# Analog_to_Digital_Con.net
KiCad netlist of a schematic drawn in Altium Designer
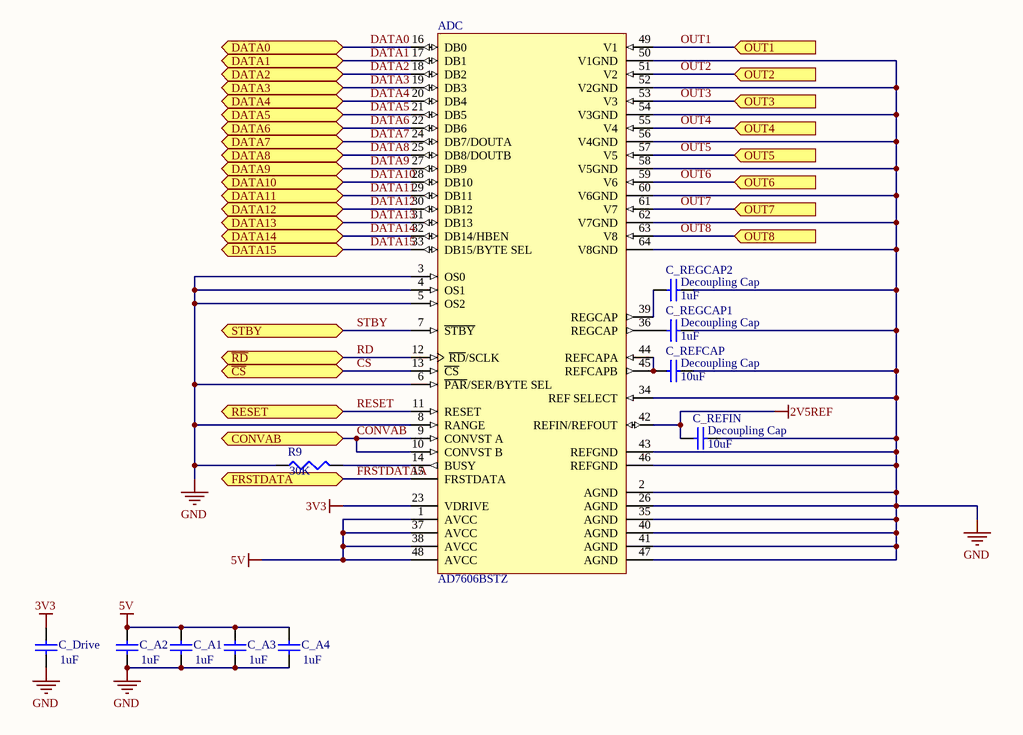
[diagram p0: Analog to Digital Con.SchDoc]

(export (version "E")
  (design (tool "Eeschema 10.0.6"))
  (components
    (comp (ref "ADC")
      (value "AD7606BSTZ")
      (footprint "ST-64-2_N")
      (fields (field (name "GENERIC PART NUMBER") "AD7606") (field (name "MANUFACTURER") "Analog Devices"))
      (libsource (lib "Analog Devices Data Converters Analog-to-Digital Converters") (part "AD7606BSTZ"))
    )
    (comp (ref "C_A1")
      (value "1uF")
      (footprint "6-0805_N")
      (description "Capacitor (Semiconductor SIM Model)")
      (fields (field (name "Comment") "Decoupling Cap") (field (name "PUBLISHER") "Altium Limited"))
      (libsource (lib "Miscellaneous Devices") (part "Cap Semi"))
    )
    (comp (ref "C_A2")
      (value "1uF")
      (footprint "6-0805_N")
      (description "Capacitor (Semiconductor SIM Model)")
      (fields (field (name "Comment") "Decoupling Cap") (field (name "PUBLISHER") "Altium Limited"))
      (libsource (lib "Miscellaneous Devices") (part "Cap Semi"))
    )
    (comp (ref "C_A3")
      (value "1uF")
      (footprint "6-0805_N")
      (description "Capacitor (Semiconductor SIM Model)")
      (fields (field (name "Comment") "Decoupling Cap") (field (name "PUBLISHER") "Altium Limited"))
      (libsource (lib "Miscellaneous Devices") (part "Cap Semi"))
    )
    (comp (ref "C_A4")
      (value "1uF")
      (footprint "6-0805_N")
      (description "Capacitor (Semiconductor SIM Model)")
      (fields (field (name "Comment") "Decoupling Cap") (field (name "PUBLISHER") "Altium Limited"))
      (libsource (lib "Miscellaneous Devices") (part "Cap Semi"))
    )
    (comp (ref "C_Drive")
      (value "1uF")
      (footprint "6-0805_N")
      (description "Capacitor (Semiconductor SIM Model)")
      (fields (field (name "Comment") "Decoupling Cap") (field (name "PUBLISHER") "Altium Limited"))
      (libsource (lib "Miscellaneous Devices") (part "Cap Semi"))
    )
    (comp (ref "C_REFCAP")
      (value "Decoupling Cap")
      (footprint "6-0805_N")
      (description "Capacitor (Semiconductor SIM Model)")
      (fields (field (name "ALTIUM_VALUE") "10uF") (field (name "PUBLISHER") "Altium Limited"))
      (libsource (lib "Miscellaneous Devices") (part "Cap Semi"))
    )
    (comp (ref "C_REFIN")
      (value "Decoupling Cap")
      (footprint "6-0805_N")
      (description "Capacitor (Semiconductor SIM Model)")
      (fields (field (name "ALTIUM_VALUE") "10uF") (field (name "PUBLISHER") "Altium Limited"))
      (libsource (lib "Miscellaneous Devices") (part "Cap Semi"))
    )
    (comp (ref "C_REGCAP1")
      (value "Decoupling Cap")
      (footprint "6-0805_N")
      (description "Capacitor (Semiconductor SIM Model)")
      (fields (field (name "ALTIUM_VALUE") "1uF") (field (name "PUBLISHER") "Altium Limited"))
      (libsource (lib "Miscellaneous Devices") (part "Cap Semi"))
    )
    (comp (ref "C_REGCAP2")
      (value "Decoupling Cap")
      (footprint "6-0805_N")
      (description "Capacitor (Semiconductor SIM Model)")
      (fields (field (name "ALTIUM_VALUE") "1uF") (field (name "PUBLISHER") "Altium Limited"))
      (libsource (lib "Miscellaneous Devices") (part "Cap Semi"))
    )
    (comp (ref "R9")
      (value "30K")
      (footprint "6-0805_N")
      (description "Resistor")
      (fields (field (name "Comment") "Res3") (field (name "PUBLISHER") "Altium Limited"))
      (libsource (lib "Miscellaneous Devices") (part "Res3"))
    )
  )
  (nets
    (net (code "1") (name "/CONVAB") (class "Default")
      (node (ref "ADC") (pin "10") (pinfunction "CONVST_B_10") (pintype "input"))
      (node (ref "ADC") (pin "9") (pinfunction "CONVST_A_9") (pintype "input"))
    )
    (net (code "2") (name "/CS") (class "Default")
      (node (ref "ADC") (pin "13") (pinfunction "~{CS}_13") (pintype "input"))
    )
    (net (code "3") (name "/DATA0") (class "Default")
      (node (ref "ADC") (pin "16") (pinfunction "DB0_16") (pintype "bidirectional"))
    )
    (net (code "4") (name "/DATA1") (class "Default")
      (node (ref "ADC") (pin "17") (pinfunction "DB1_17") (pintype "bidirectional"))
    )
    (net (code "5") (name "/DATA2") (class "Default")
      (node (ref "ADC") (pin "18") (pinfunction "DB2_18") (pintype "bidirectional"))
    )
    (net (code "6") (name "/DATA3") (class "Default")
      (node (ref "ADC") (pin "19") (pinfunction "DB3_19") (pintype "bidirectional"))
    )
    (net (code "7") (name "/DATA4") (class "Default")
      (node (ref "ADC") (pin "20") (pinfunction "DB4_20") (pintype "bidirectional"))
    )
    (net (code "8") (name "/DATA5") (class "Default")
      (node (ref "ADC") (pin "21") (pinfunction "DB5_21") (pintype "bidirectional"))
    )
    (net (code "9") (name "/DATA6") (class "Default")
      (node (ref "ADC") (pin "22") (pinfunction "DB6_22") (pintype "bidirectional"))
    )
    (net (code "10") (name "/DATA7") (class "Default")
      (node (ref "ADC") (pin "24") (pinfunction "DB7/DOUTA_24") (pintype "bidirectional"))
    )
    (net (code "11") (name "/DATA8") (class "Default")
      (node (ref "ADC") (pin "25") (pinfunction "DB8/DOUTB_25") (pintype "bidirectional"))
    )
    (net (code "12") (name "/DATA9") (class "Default")
      (node (ref "ADC") (pin "27") (pinfunction "DB9_27") (pintype "bidirectional"))
    )
    (net (code "13") (name "/DATA10") (class "Default")
      (node (ref "ADC") (pin "28") (pinfunction "DB10_28") (pintype "bidirectional"))
    )
    (net (code "14") (name "/DATA11") (class "Default")
      (node (ref "ADC") (pin "29") (pinfunction "DB11_29") (pintype "bidirectional"))
    )
    (net (code "15") (name "/DATA12") (class "Default")
      (node (ref "ADC") (pin "30") (pinfunction "DB12_30") (pintype "bidirectional"))
    )
    (net (code "16") (name "/DATA13") (class "Default")
      (node (ref "ADC") (pin "31") (pinfunction "DB13_31") (pintype "bidirectional"))
    )
    (net (code "17") (name "/DATA14") (class "Default")
      (node (ref "ADC") (pin "32") (pinfunction "DB14/HBEN_32") (pintype "bidirectional"))
    )
    (net (code "18") (name "/DATA15") (class "Default")
      (node (ref "ADC") (pin "33") (pinfunction "DB15/BYTE_SEL_33") (pintype "bidirectional"))
    )
    (net (code "19") (name "/FRSTDATAA") (class "Default")
      (node (ref "ADC") (pin "15") (pinfunction "FRSTDATA_15") (pintype "tri_state"))
    )
    (net (code "20") (name "/OUT1") (class "Default")
      (node (ref "ADC") (pin "49") (pinfunction "V1_49") (pintype "input"))
    )
    (net (code "21") (name "/OUT2") (class "Default")
      (node (ref "ADC") (pin "51") (pinfunction "V2_51") (pintype "input"))
    )
    (net (code "22") (name "/OUT3") (class "Default")
      (node (ref "ADC") (pin "53") (pinfunction "V3_53") (pintype "input"))
    )
    (net (code "23") (name "/OUT4") (class "Default")
      (node (ref "ADC") (pin "55") (pinfunction "V4_55") (pintype "input"))
    )
    (net (code "24") (name "/OUT5") (class "Default")
      (node (ref "ADC") (pin "57") (pinfunction "V5_57") (pintype "input"))
    )
    (net (code "25") (name "/OUT6") (class "Default")
      (node (ref "ADC") (pin "59") (pinfunction "V6_59") (pintype "input"))
    )
    (net (code "26") (name "/OUT7") (class "Default")
      (node (ref "ADC") (pin "61") (pinfunction "V7_61") (pintype "input"))
    )
    (net (code "27") (name "/OUT8") (class "Default")
      (node (ref "ADC") (pin "63") (pinfunction "V8_63") (pintype "input"))
    )
    (net (code "28") (name "/RD") (class "Default")
      (node (ref "ADC") (pin "12") (pinfunction "~{RD}/SCLK_12") (pintype "input"))
    )
    (net (code "29") (name "/RESET") (class "Default")
      (node (ref "ADC") (pin "11") (pinfunction "RESET_11") (pintype "input"))
    )
    (net (code "30") (name "/STBY") (class "Default")
      (node (ref "ADC") (pin "7") (pinfunction "~{STBY}_7") (pintype "input"))
    )
    (net (code "31") (name "2V5REF") (class "Default")
      (node (ref "ADC") (pin "42") (pinfunction "REFIN/REFOUT_42") (pintype "bidirectional"))
      (node (ref "C_REFIN") (pin "2") (pinfunction "2_2") (pintype "passive"))
    )
    (net (code "32") (name "3V3") (class "Default")
      (node (ref "ADC") (pin "23") (pinfunction "VDRIVE_23") (pintype "power_in"))
      (node (ref "C_Drive") (pin "1") (pinfunction "1_1") (pintype "passive"))
    )
    (net (code "33") (name "5V") (class "Default")
      (node (ref "ADC") (pin "1") (pinfunction "AVCC_1") (pintype "power_in"))
      (node (ref "ADC") (pin "37") (pinfunction "AVCC_37") (pintype "power_in"))
      (node (ref "ADC") (pin "38") (pinfunction "AVCC_38") (pintype "power_in"))
      (node (ref "ADC") (pin "48") (pinfunction "AVCC_48") (pintype "power_in"))
      (node (ref "C_A1") (pin "1") (pinfunction "1_1") (pintype "passive"))
      (node (ref "C_A2") (pin "1") (pinfunction "1_1") (pintype "passive"))
      (node (ref "C_A3") (pin "1") (pinfunction "1_1") (pintype "passive"))
      (node (ref "C_A4") (pin "1") (pinfunction "1_1") (pintype "passive"))
    )
    (net (code "34") (name "GND") (class "Default")
      (node (ref "ADC") (pin "2") (pinfunction "AGND_2") (pintype "power_in"))
      (node (ref "ADC") (pin "26") (pinfunction "AGND_26") (pintype "power_in"))
      (node (ref "ADC") (pin "3") (pinfunction "OS0_3") (pintype "input"))
      (node (ref "ADC") (pin "34") (pinfunction "REF_SELECT_34") (pintype "input"))
      (node (ref "ADC") (pin "35") (pinfunction "AGND_35") (pintype "power_in"))
      (node (ref "ADC") (pin "4") (pinfunction "OS1_4") (pintype "input"))
      (node (ref "ADC") (pin "40") (pinfunction "AGND_40") (pintype "power_in"))
      (node (ref "ADC") (pin "41") (pinfunction "AGND_41") (pintype "power_in"))
      (node (ref "ADC") (pin "43") (pinfunction "REFGND_43") (pintype "power_in"))
      (node (ref "ADC") (pin "46") (pinfunction "REFGND_46") (pintype "power_in"))
      (node (ref "ADC") (pin "47") (pinfunction "AGND_47") (pintype "power_in"))
      (node (ref "ADC") (pin "5") (pinfunction "OS2_5") (pintype "input"))
      (node (ref "ADC") (pin "50") (pinfunction "V1GND_50") (pintype "power_in"))
      (node (ref "ADC") (pin "52") (pinfunction "V2GND_52") (pintype "power_in"))
      (node (ref "ADC") (pin "54") (pinfunction "V3GND_54") (pintype "power_in"))
      (node (ref "ADC") (pin "56") (pinfunction "V4GND_56") (pintype "power_in"))
      (node (ref "ADC") (pin "58") (pinfunction "V5GND_58") (pintype "power_in"))
      (node (ref "ADC") (pin "6") (pinfunction "~{PAR}/SER/BYTE_SEL_6") (pintype "input"))
      (node (ref "ADC") (pin "60") (pinfunction "V6GND_60") (pintype "power_in"))
      (node (ref "ADC") (pin "62") (pinfunction "V7GND_62") (pintype "power_in"))
      (node (ref "ADC") (pin "64") (pinfunction "V8GND_64") (pintype "power_in"))
      (node (ref "ADC") (pin "8") (pinfunction "RANGE_8") (pintype "input"))
      (node (ref "C_A1") (pin "2") (pinfunction "2_2") (pintype "passive"))
      (node (ref "C_A2") (pin "2") (pinfunction "2_2") (pintype "passive"))
      (node (ref "C_A3") (pin "2") (pinfunction "2_2") (pintype "passive"))
      (node (ref "C_A4") (pin "2") (pinfunction "2_2") (pintype "passive"))
      (node (ref "C_Drive") (pin "2") (pinfunction "2_2") (pintype "passive"))
      (node (ref "C_REFCAP") (pin "1") (pinfunction "1_1") (pintype "passive"))
      (node (ref "C_REFIN") (pin "1") (pinfunction "1_1") (pintype "passive"))
      (node (ref "C_REGCAP1") (pin "1") (pinfunction "1_1") (pintype "passive"))
      (node (ref "C_REGCAP2") (pin "1") (pinfunction "1_1") (pintype "passive"))
      (node (ref "R9") (pin "1") (pinfunction "1_1") (pintype "passive"))
    )
    (net (code "35") (name "Net-(ADC-BUSY)") (class "Default")
      (node (ref "ADC") (pin "14") (pinfunction "BUSY_14") (pintype "output"))
      (node (ref "R9") (pin "2") (pinfunction "2_2") (pintype "passive"))
    )
    (net (code "36") (name "Net-(ADC-REFCAPA)") (class "Default")
      (node (ref "ADC") (pin "44") (pinfunction "REFCAPA_44") (pintype "input"))
      (node (ref "ADC") (pin "45") (pinfunction "REFCAPB_45") (pintype "output"))
      (node (ref "C_REFCAP") (pin "2") (pinfunction "2_2") (pintype "passive"))
    )
    (net (code "37") (name "Net-(ADC-REGCAP-Pad36)") (class "Default")
      (node (ref "ADC") (pin "36") (pinfunction "REGCAP_36") (pintype "output"))
      (node (ref "C_REGCAP1") (pin "2") (pinfunction "2_2") (pintype "passive"))
    )
    (net (code "38") (name "Net-(ADC-REGCAP-Pad39)") (class "Default")
      (node (ref "ADC") (pin "39") (pinfunction "REGCAP_39") (pintype "output"))
      (node (ref "C_REGCAP2") (pin "2") (pinfunction "2_2") (pintype "passive"))
    )
  )
)
